# fpga.net
KiCad netlist of a schematic drawn in EAGLE
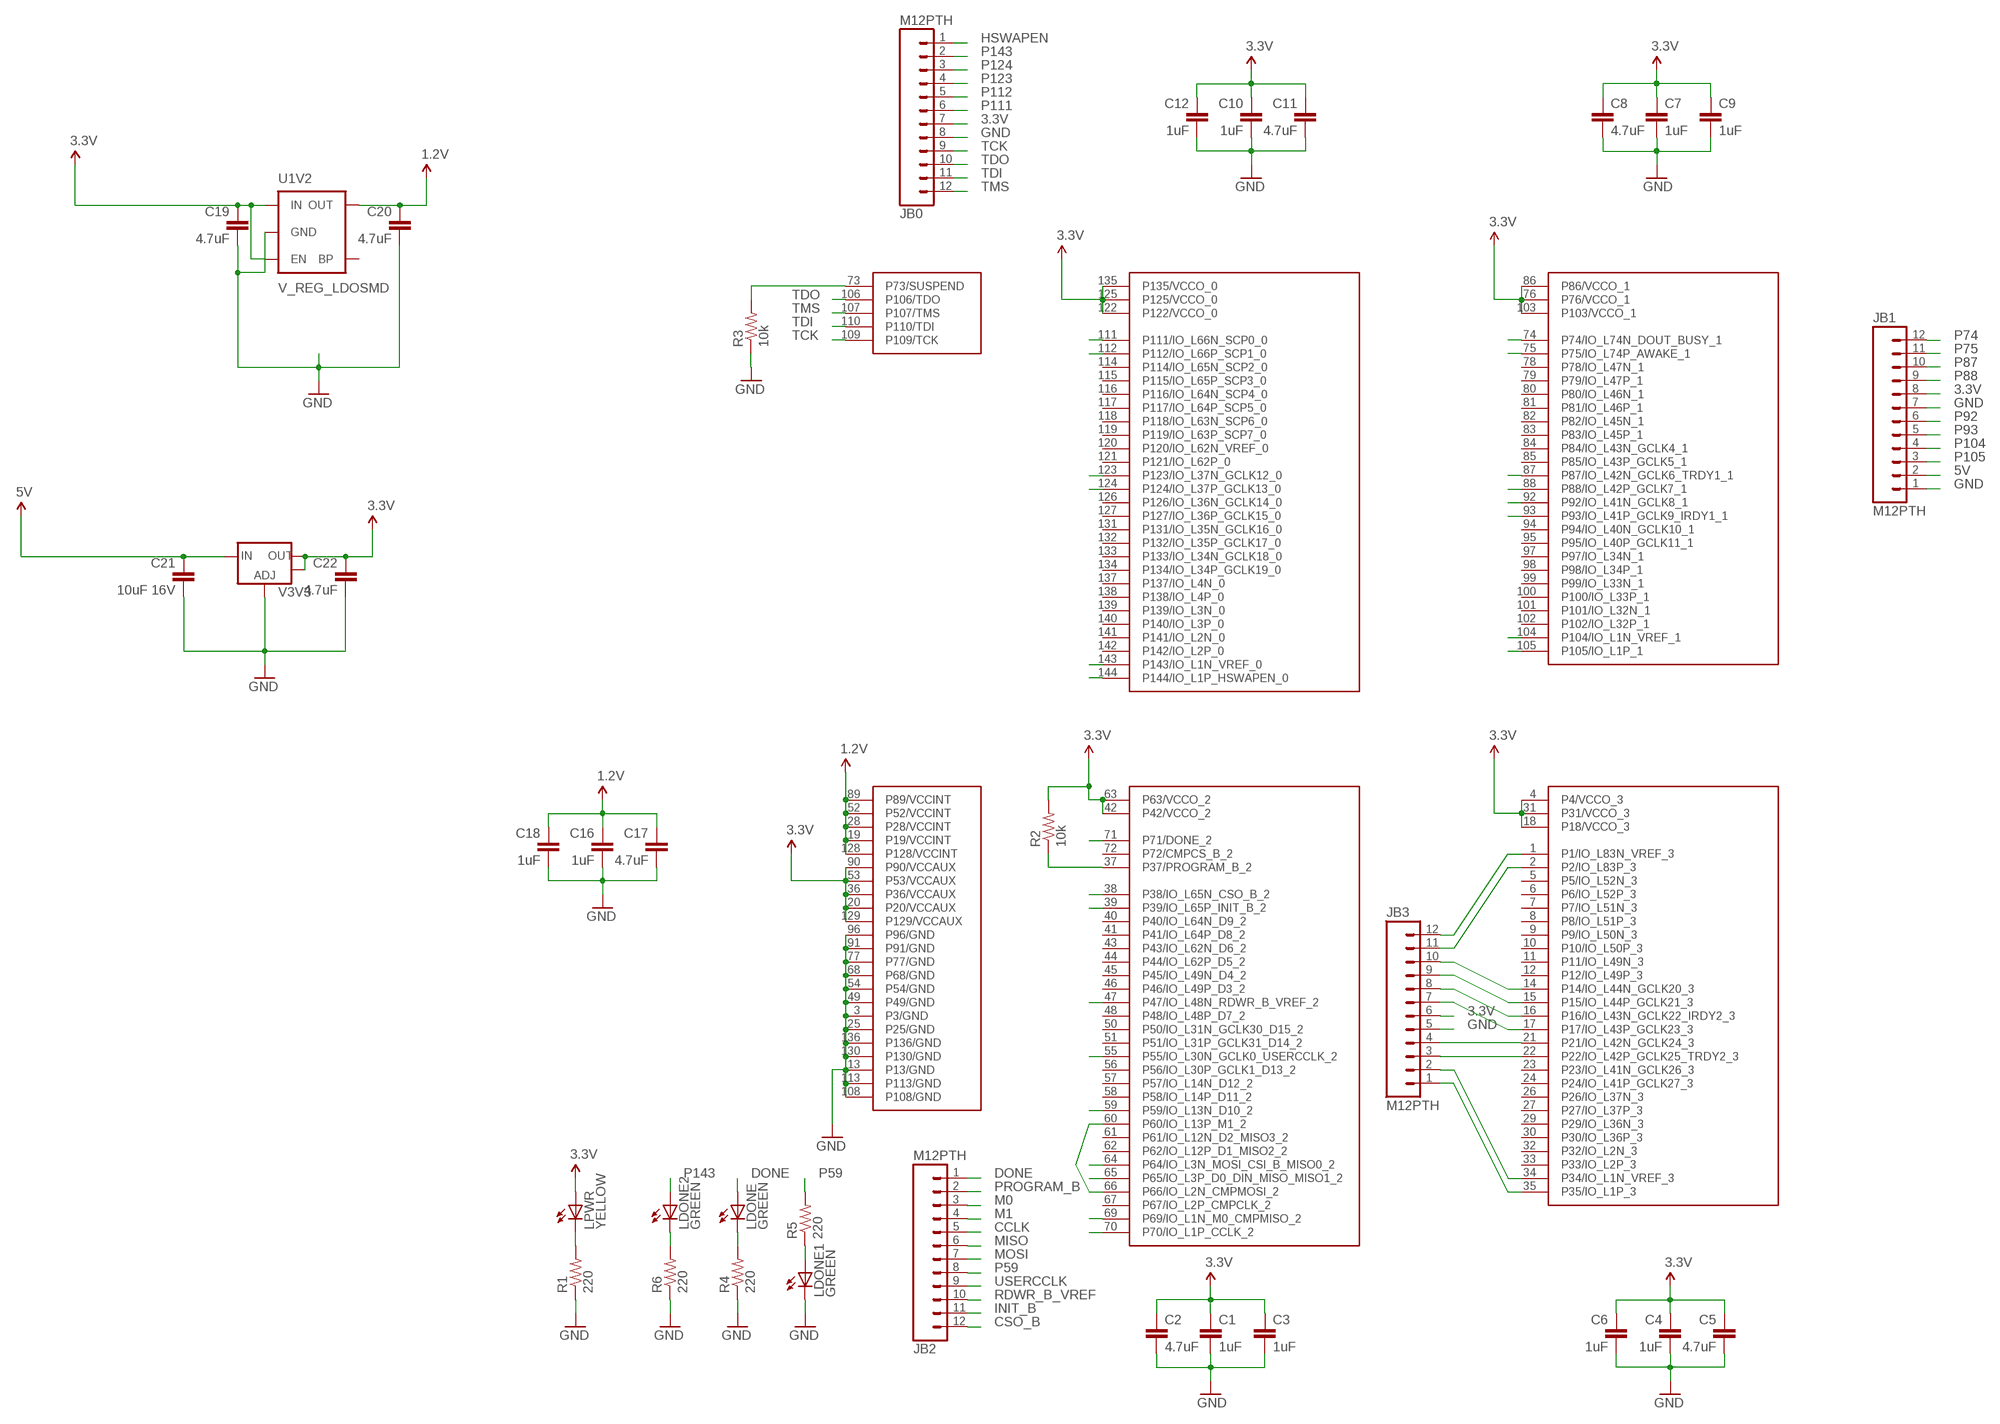
[diagram p0: schematic, sheet 1]

(export (version "E")
  (design (tool "Eeschema 10.0.6"))
  (components
    (comp (ref "C1")
      (value "1uF")
      (footprint "eagle-import:0402-CAP")
      (libsource (lib "eagle-import") (part "CAP0402-CAP"))
    )
    (comp (ref "C2")
      (value "4.7uF")
      (footprint "eagle-import:0805")
      (libsource (lib "eagle-import") (part "kmod_CAP0805"))
    )
    (comp (ref "C3")
      (value "1uF")
      (footprint "eagle-import:0402-CAP")
      (libsource (lib "eagle-import") (part "CAP0402-CAP"))
    )
    (comp (ref "C4")
      (value "1uF")
      (footprint "eagle-import:0402-CAP")
      (libsource (lib "eagle-import") (part "CAP0402-CAP"))
    )
    (comp (ref "C5")
      (value "4.7uF")
      (footprint "eagle-import:0805")
      (libsource (lib "eagle-import") (part "kmod_CAP0805"))
    )
    (comp (ref "C6")
      (value "1uF")
      (footprint "eagle-import:0402-CAP")
      (libsource (lib "eagle-import") (part "CAP0402-CAP"))
    )
    (comp (ref "C7")
      (value "1uF")
      (footprint "eagle-import:0402-CAP")
      (libsource (lib "eagle-import") (part "CAP0402-CAP"))
    )
    (comp (ref "C8")
      (value "4.7uF")
      (footprint "eagle-import:0805")
      (libsource (lib "eagle-import") (part "kmod_CAP0805"))
    )
    (comp (ref "C9")
      (value "1uF")
      (footprint "eagle-import:0402-CAP")
      (libsource (lib "eagle-import") (part "CAP0402-CAP"))
    )
    (comp (ref "C10")
      (value "1uF")
      (footprint "eagle-import:0402-CAP")
      (libsource (lib "eagle-import") (part "CAP0402-CAP"))
    )
    (comp (ref "C11")
      (value "4.7uF")
      (footprint "eagle-import:0805")
      (libsource (lib "eagle-import") (part "kmod_CAP0805"))
    )
    (comp (ref "C12")
      (value "1uF")
      (footprint "eagle-import:0402-CAP")
      (libsource (lib "eagle-import") (part "CAP0402-CAP"))
    )
    (comp (ref "C16")
      (value "1uF")
      (footprint "eagle-import:0402-CAP")
      (libsource (lib "eagle-import") (part "CAP0402-CAP"))
    )
    (comp (ref "C17")
      (value "4.7uF")
      (footprint "eagle-import:0805")
      (libsource (lib "eagle-import") (part "kmod_CAP0805"))
    )
    (comp (ref "C18")
      (value "1uF")
      (footprint "eagle-import:0402-CAP")
      (libsource (lib "eagle-import") (part "CAP0402-CAP"))
    )
    (comp (ref "C19")
      (value "4.7uF")
      (footprint "eagle-import:0805")
      (libsource (lib "eagle-import") (part "kmod_CAP0805"))
    )
    (comp (ref "C20")
      (value "4.7uF")
      (footprint "eagle-import:0805")
      (libsource (lib "eagle-import") (part "kmod_CAP0805"))
    )
    (comp (ref "C21")
      (value "10uF 16V")
      (footprint "eagle-import:0805")
      (libsource (lib "eagle-import") (part "kmod_CAP0805"))
    )
    (comp (ref "C22")
      (value "4.7uF")
      (footprint "eagle-import:0805")
      (libsource (lib "eagle-import") (part "kmod_CAP0805"))
    )
    (comp (ref "JB0")
      (value "M12PTH")
      (footprint "eagle-import:1X12")
      (libsource (lib "eagle-import") (part "M12PTH"))
    )
    (comp (ref "JB1")
      (value "M12PTH")
      (footprint "eagle-import:1X12")
      (libsource (lib "eagle-import") (part "M12PTH"))
    )
    (comp (ref "JB2")
      (value "M12PTH")
      (footprint "eagle-import:1X12")
      (libsource (lib "eagle-import") (part "M12PTH"))
    )
    (comp (ref "JB3")
      (value "M12PTH")
      (footprint "eagle-import:1X12")
      (libsource (lib "eagle-import") (part "M12PTH"))
    )
    (comp (ref "LDONE")
      (value "GREEN")
      (footprint "eagle-import:0603_LED")
      (libsource (lib "eagle-import") (part "LED0603"))
    )
    (comp (ref "LDONE1")
      (value "GREEN")
      (footprint "eagle-import:0603_LED")
      (libsource (lib "eagle-import") (part "LED0603"))
    )
    (comp (ref "LDONE2")
      (value "GREEN")
      (footprint "eagle-import:0603_LED")
      (libsource (lib "eagle-import") (part "LED0603"))
    )
    (comp (ref "LPWR")
      (value "YELLOW")
      (footprint "eagle-import:0603_LED")
      (libsource (lib "eagle-import") (part "LED0603"))
    )
    (comp (ref "R1")
      (value "220")
      (footprint "eagle-import:0603-RES")
      (libsource (lib "eagle-import") (part "RESISTOR0603"))
    )
    (comp (ref "R2")
      (value "10k")
      (footprint "eagle-import:0603-RES")
      (libsource (lib "eagle-import") (part "RESISTOR0603"))
    )
    (comp (ref "R3")
      (value "10k")
      (footprint "eagle-import:0603-RES")
      (libsource (lib "eagle-import") (part "RESISTOR0603"))
    )
    (comp (ref "R4")
      (value "220")
      (footprint "eagle-import:0603-RES")
      (libsource (lib "eagle-import") (part "RESISTOR0603"))
    )
    (comp (ref "R5")
      (value "220")
      (footprint "eagle-import:0603-RES")
      (libsource (lib "eagle-import") (part "RESISTOR0603"))
    )
    (comp (ref "R6")
      (value "220")
      (footprint "eagle-import:0603-RES")
      (libsource (lib "eagle-import") (part "RESISTOR0603"))
    )
    (comp (ref "U$1")
      (value "XC6SLX-TQ144")
      (footprint "eagle-import:XILNX_TQ144")
      (libsource (lib "eagle-import") (part "XC6SLX-TQ144"))
    )
    (comp (ref "U1V2")
      (value "V_REG_LDOSMD")
      (footprint "eagle-import:SOT23-5")
      (libsource (lib "eagle-import") (part "V_REG_LDOSMD"))
    )
    (comp (ref "V3V3")
      (value "V_REG_LM1117SOT223")
      (footprint "eagle-import:SOT223")
      (libsource (lib "eagle-import") (part "V_REG_LM1117SOT223"))
    )
  )
  (nets
    (net (code "1") (name "/CCLK") (class "Default")
      (node (ref "JB2") (pin "5") (pinfunction "5_5") (pintype "passive"))
      (node (ref "U$1") (pin "70") (pinfunction "P70/IO_L1P_CCLK_2_70") (pintype "bidirectional"))
    )
    (net (code "2") (name "/CSO_B") (class "Default")
      (node (ref "JB2") (pin "12") (pinfunction "12_12") (pintype "passive"))
      (node (ref "U$1") (pin "38") (pinfunction "P38/IO_L65N_CSO_B_2_38") (pintype "bidirectional"))
    )
    (net (code "3") (name "/DONE") (class "Default")
      (node (ref "JB2") (pin "1") (pinfunction "1_1") (pintype "passive"))
      (node (ref "LDONE") (pin "A") (pinfunction "A_A") (pintype "passive"))
      (node (ref "U$1") (pin "71") (pinfunction "P71/DONE_2_71") (pintype "bidirectional"))
    )
    (net (code "4") (name "/HSWAPEN") (class "Default")
      (node (ref "JB0") (pin "1") (pinfunction "1_1") (pintype "passive"))
      (node (ref "U$1") (pin "144") (pinfunction "P144/IO_L1P_HSWAPEN_0_144") (pintype "bidirectional"))
    )
    (net (code "5") (name "/INIT_B") (class "Default")
      (node (ref "JB2") (pin "11") (pinfunction "11_11") (pintype "passive"))
      (node (ref "U$1") (pin "39") (pinfunction "P39/IO_L65P_INIT_B_2_39") (pintype "bidirectional"))
    )
    (net (code "6") (name "/M0") (class "Default")
      (node (ref "JB2") (pin "3") (pinfunction "3_3") (pintype "passive"))
      (node (ref "U$1") (pin "69") (pinfunction "P69/IO_L1N_M0_CMPMISO_2_69") (pintype "bidirectional"))
    )
    (net (code "7") (name "/M1") (class "Default")
      (node (ref "JB2") (pin "4") (pinfunction "4_4") (pintype "passive"))
      (node (ref "U$1") (pin "60") (pinfunction "P60/IO_L13P_M1_2_60") (pintype "bidirectional"))
      (node (ref "U$1") (pin "66") (pinfunction "P66/IO_L2N_CMPMOSI_2_66") (pintype "bidirectional"))
    )
    (net (code "8") (name "/MISO") (class "Default")
      (node (ref "JB2") (pin "6") (pinfunction "6_6") (pintype "passive"))
      (node (ref "U$1") (pin "65") (pinfunction "P65/IO_L3P_D0_DIN_MISO_MISO1_2_65") (pintype "bidirectional"))
    )
    (net (code "9") (name "/MOSI") (class "Default")
      (node (ref "JB2") (pin "7") (pinfunction "7_7") (pintype "passive"))
      (node (ref "U$1") (pin "64") (pinfunction "P64/IO_L3N_MOSI_CSI_B_MISO0_2_64") (pintype "bidirectional"))
    )
    (net (code "10") (name "/P59") (class "Default")
      (node (ref "JB2") (pin "8") (pinfunction "8_8") (pintype "passive"))
      (node (ref "R5") (pin "2") (pinfunction "2_2") (pintype "passive"))
      (node (ref "U$1") (pin "59") (pinfunction "P59/IO_L13N_D10_2_59") (pintype "bidirectional"))
    )
    (net (code "11") (name "/P74") (class "Default")
      (node (ref "JB1") (pin "12") (pinfunction "12_12") (pintype "passive"))
      (node (ref "U$1") (pin "74") (pinfunction "P74/IO_L74N_DOUT_BUSY_1_74") (pintype "bidirectional"))
    )
    (net (code "12") (name "/P75") (class "Default")
      (node (ref "JB1") (pin "11") (pinfunction "11_11") (pintype "passive"))
      (node (ref "U$1") (pin "75") (pinfunction "P75/IO_L74P_AWAKE_1_75") (pintype "bidirectional"))
    )
    (net (code "13") (name "/P87") (class "Default")
      (node (ref "JB1") (pin "10") (pinfunction "10_10") (pintype "passive"))
      (node (ref "U$1") (pin "87") (pinfunction "P87/IO_L42N_GCLK6_TRDY1_1_87") (pintype "bidirectional"))
    )
    (net (code "14") (name "/P88") (class "Default")
      (node (ref "JB1") (pin "9") (pinfunction "9_9") (pintype "passive"))
      (node (ref "U$1") (pin "88") (pinfunction "P88/IO_L42P_GCLK7_1_88") (pintype "bidirectional"))
    )
    (net (code "15") (name "/P92") (class "Default")
      (node (ref "JB1") (pin "6") (pinfunction "6_6") (pintype "passive"))
      (node (ref "U$1") (pin "92") (pinfunction "P92/IO_L41N_GCLK8_1_92") (pintype "bidirectional"))
    )
    (net (code "16") (name "/P93") (class "Default")
      (node (ref "JB1") (pin "5") (pinfunction "5_5") (pintype "passive"))
      (node (ref "U$1") (pin "93") (pinfunction "P93/IO_L41P_GCLK9_IRDY1_1_93") (pintype "bidirectional"))
    )
    (net (code "17") (name "/P104") (class "Default")
      (node (ref "JB1") (pin "4") (pinfunction "4_4") (pintype "passive"))
      (node (ref "U$1") (pin "104") (pinfunction "P104/IO_L1N_VREF_1_104") (pintype "bidirectional"))
    )
    (net (code "18") (name "/P105") (class "Default")
      (node (ref "JB1") (pin "3") (pinfunction "3_3") (pintype "passive"))
      (node (ref "U$1") (pin "105") (pinfunction "P105/IO_L1P_1_105") (pintype "bidirectional"))
    )
    (net (code "19") (name "/P111") (class "Default")
      (node (ref "JB0") (pin "6") (pinfunction "6_6") (pintype "passive"))
      (node (ref "U$1") (pin "111") (pinfunction "P111/IO_L66N_SCP0_0_111") (pintype "bidirectional"))
    )
    (net (code "20") (name "/P112") (class "Default")
      (node (ref "JB0") (pin "5") (pinfunction "5_5") (pintype "passive"))
      (node (ref "U$1") (pin "112") (pinfunction "P112/IO_L66P_SCP1_0_112") (pintype "bidirectional"))
    )
    (net (code "21") (name "/P123") (class "Default")
      (node (ref "JB0") (pin "4") (pinfunction "4_4") (pintype "passive"))
      (node (ref "U$1") (pin "123") (pinfunction "P123/IO_L37N_GCLK12_0_123") (pintype "bidirectional"))
    )
    (net (code "22") (name "/P124") (class "Default")
      (node (ref "JB0") (pin "3") (pinfunction "3_3") (pintype "passive"))
      (node (ref "U$1") (pin "124") (pinfunction "P124/IO_L37P_GCLK13_0_124") (pintype "bidirectional"))
    )
    (net (code "23") (name "/P143") (class "Default")
      (node (ref "JB0") (pin "2") (pinfunction "2_2") (pintype "passive"))
      (node (ref "LDONE2") (pin "A") (pinfunction "A_A") (pintype "passive"))
      (node (ref "U$1") (pin "143") (pinfunction "P143/IO_L1N_VREF_0_143") (pintype "bidirectional"))
    )
    (net (code "24") (name "/PROGRAM_B") (class "Default")
      (node (ref "JB2") (pin "2") (pinfunction "2_2") (pintype "passive"))
      (node (ref "R2") (pin "1") (pinfunction "1_1") (pintype "passive"))
      (node (ref "U$1") (pin "37") (pinfunction "P37/PROGRAM_B_2_37") (pintype "bidirectional"))
    )
    (net (code "25") (name "/RDWR_B_VREF") (class "Default")
      (node (ref "JB2") (pin "10") (pinfunction "10_10") (pintype "passive"))
      (node (ref "U$1") (pin "47") (pinfunction "P47/IO_L48N_RDWR_B_VREF_2_47") (pintype "bidirectional"))
    )
    (net (code "26") (name "/TCK") (class "Default")
      (node (ref "JB0") (pin "9") (pinfunction "9_9") (pintype "passive"))
      (node (ref "U$1") (pin "109") (pinfunction "P109/TCK_109") (pintype "bidirectional"))
    )
    (net (code "27") (name "/TDI") (class "Default")
      (node (ref "JB0") (pin "11") (pinfunction "11_11") (pintype "passive"))
      (node (ref "U$1") (pin "110") (pinfunction "P110/TDI_110") (pintype "bidirectional"))
    )
    (net (code "28") (name "/TDO") (class "Default")
      (node (ref "JB0") (pin "10") (pinfunction "10_10") (pintype "passive"))
      (node (ref "U$1") (pin "106") (pinfunction "P106/TDO_106") (pintype "bidirectional"))
    )
    (net (code "29") (name "/TMS") (class "Default")
      (node (ref "JB0") (pin "12") (pinfunction "12_12") (pintype "passive"))
      (node (ref "U$1") (pin "107") (pinfunction "P107/TMS_107") (pintype "bidirectional"))
    )
    (net (code "30") (name "/USERCCLK") (class "Default")
      (node (ref "JB2") (pin "9") (pinfunction "9_9") (pintype "passive"))
      (node (ref "U$1") (pin "55") (pinfunction "P55/IO_L30N_GCLK0_USERCCLK_2_55") (pintype "bidirectional"))
    )
    (net (code "31") (name "1.2V") (class "Default")
      (node (ref "C16") (pin "1") (pinfunction "1_1") (pintype "passive"))
      (node (ref "C17") (pin "1") (pinfunction "1_1") (pintype "passive"))
      (node (ref "C18") (pin "1") (pinfunction "1_1") (pintype "passive"))
      (node (ref "C20") (pin "1") (pinfunction "1_1") (pintype "passive"))
      (node (ref "U$1") (pin "128") (pinfunction "P128/VCCINT_128") (pintype "bidirectional"))
      (node (ref "U$1") (pin "19") (pinfunction "P19/VCCINT_19") (pintype "bidirectional"))
      (node (ref "U$1") (pin "28") (pinfunction "P28/VCCINT_28") (pintype "bidirectional"))
      (node (ref "U$1") (pin "52") (pinfunction "P52/VCCINT_52") (pintype "bidirectional"))
      (node (ref "U$1") (pin "89") (pinfunction "P89/VCCINT_89") (pintype "bidirectional"))
      (node (ref "U1V2") (pin "5") (pinfunction "OUT_5") (pintype "passive"))
    )
    (net (code "32") (name "3.3V") (class "Default")
      (node (ref "C1") (pin "1") (pinfunction "1_1") (pintype "passive"))
      (node (ref "C10") (pin "1") (pinfunction "1_1") (pintype "passive"))
      (node (ref "C11") (pin "1") (pinfunction "1_1") (pintype "passive"))
      (node (ref "C12") (pin "1") (pinfunction "1_1") (pintype "passive"))
      (node (ref "C19") (pin "1") (pinfunction "1_1") (pintype "passive"))
      (node (ref "C2") (pin "1") (pinfunction "1_1") (pintype "passive"))
      (node (ref "C22") (pin "1") (pinfunction "1_1") (pintype "passive"))
      (node (ref "C3") (pin "1") (pinfunction "1_1") (pintype "passive"))
      (node (ref "C4") (pin "1") (pinfunction "1_1") (pintype "passive"))
      (node (ref "C5") (pin "1") (pinfunction "1_1") (pintype "passive"))
      (node (ref "C6") (pin "1") (pinfunction "1_1") (pintype "passive"))
      (node (ref "C7") (pin "1") (pinfunction "1_1") (pintype "passive"))
      (node (ref "C8") (pin "1") (pinfunction "1_1") (pintype "passive"))
      (node (ref "C9") (pin "1") (pinfunction "1_1") (pintype "passive"))
      (node (ref "JB0") (pin "7") (pinfunction "7_7") (pintype "passive"))
      (node (ref "JB1") (pin "8") (pinfunction "8_8") (pintype "passive"))
      (node (ref "JB3") (pin "6") (pinfunction "6_6") (pintype "passive"))
      (node (ref "LPWR") (pin "A") (pinfunction "A_A") (pintype "passive"))
      (node (ref "R2") (pin "2") (pinfunction "2_2") (pintype "passive"))
      (node (ref "U$1") (pin "103") (pinfunction "P103/VCCO_1_103") (pintype "bidirectional"))
      (node (ref "U$1") (pin "122") (pinfunction "P122/VCCO_0_122") (pintype "bidirectional"))
      (node (ref "U$1") (pin "125") (pinfunction "P125/VCCO_0_125") (pintype "bidirectional"))
      (node (ref "U$1") (pin "129") (pinfunction "P129/VCCAUX_129") (pintype "bidirectional"))
      (node (ref "U$1") (pin "135") (pinfunction "P135/VCCO_0_135") (pintype "bidirectional"))
      (node (ref "U$1") (pin "18") (pinfunction "P18/VCCO_3_18") (pintype "bidirectional"))
      (node (ref "U$1") (pin "20") (pinfunction "P20/VCCAUX_20") (pintype "bidirectional"))
      (node (ref "U$1") (pin "31") (pinfunction "P31/VCCO_3_31") (pintype "bidirectional"))
      (node (ref "U$1") (pin "36") (pinfunction "P36/VCCAUX_36") (pintype "bidirectional"))
      (node (ref "U$1") (pin "4") (pinfunction "P4/VCCO_3_4") (pintype "bidirectional"))
      (node (ref "U$1") (pin "42") (pinfunction "P42/VCCO_2_42") (pintype "bidirectional"))
      (node (ref "U$1") (pin "53") (pinfunction "P53/VCCAUX_53") (pintype "bidirectional"))
      (node (ref "U$1") (pin "63") (pinfunction "P63/VCCO_2_63") (pintype "bidirectional"))
      (node (ref "U$1") (pin "76") (pinfunction "P76/VCCO_1_76") (pintype "bidirectional"))
      (node (ref "U$1") (pin "86") (pinfunction "P86/VCCO_1_86") (pintype "bidirectional"))
      (node (ref "U$1") (pin "90") (pinfunction "P90/VCCAUX_90") (pintype "bidirectional"))
      (node (ref "U1V2") (pin "1") (pinfunction "IN_1") (pintype "input"))
      (node (ref "U1V2") (pin "3") (pinfunction "EN_3") (pintype "input"))
      (node (ref "V3V3") (pin "2") (pinfunction "OUT_2") (pintype "output"))
      (node (ref "V3V3") (pin "4") (pinfunction "OUT_4") (pintype "output"))
    )
    (net (code "33") (name "5V") (class "Default")
      (node (ref "C21") (pin "1") (pinfunction "1_1") (pintype "passive"))
      (node (ref "JB1") (pin "2") (pinfunction "2_2") (pintype "passive"))
      (node (ref "V3V3") (pin "3") (pinfunction "IN_3") (pintype "input"))
    )
    (net (code "34") (name "GND") (class "Default")
      (node (ref "C1") (pin "2") (pinfunction "2_2") (pintype "passive"))
      (node (ref "C10") (pin "2") (pinfunction "2_2") (pintype "passive"))
      (node (ref "C11") (pin "2") (pinfunction "2_2") (pintype "passive"))
      (node (ref "C12") (pin "2") (pinfunction "2_2") (pintype "passive"))
      (node (ref "C16") (pin "2") (pinfunction "2_2") (pintype "passive"))
      (node (ref "C17") (pin "2") (pinfunction "2_2") (pintype "passive"))
      (node (ref "C18") (pin "2") (pinfunction "2_2") (pintype "passive"))
      (node (ref "C19") (pin "2") (pinfunction "2_2") (pintype "passive"))
      (node (ref "C2") (pin "2") (pinfunction "2_2") (pintype "passive"))
      (node (ref "C20") (pin "2") (pinfunction "2_2") (pintype "passive"))
      (node (ref "C21") (pin "2") (pinfunction "2_2") (pintype "passive"))
      (node (ref "C22") (pin "2") (pinfunction "2_2") (pintype "passive"))
      (node (ref "C3") (pin "2") (pinfunction "2_2") (pintype "passive"))
      (node (ref "C4") (pin "2") (pinfunction "2_2") (pintype "passive"))
      (node (ref "C5") (pin "2") (pinfunction "2_2") (pintype "passive"))
      (node (ref "C6") (pin "2") (pinfunction "2_2") (pintype "passive"))
      (node (ref "C7") (pin "2") (pinfunction "2_2") (pintype "passive"))
      (node (ref "C8") (pin "2") (pinfunction "2_2") (pintype "passive"))
      (node (ref "C9") (pin "2") (pinfunction "2_2") (pintype "passive"))
      (node (ref "JB0") (pin "8") (pinfunction "8_8") (pintype "passive"))
      (node (ref "JB1") (pin "1") (pinfunction "1_1") (pintype "passive"))
      (node (ref "JB1") (pin "7") (pinfunction "7_7") (pintype "passive"))
      (node (ref "JB3") (pin "5") (pinfunction "5_5") (pintype "passive"))
      (node (ref "LDONE1") (pin "C") (pinfunction "C_C") (pintype "passive"))
      (node (ref "R1") (pin "1") (pinfunction "1_1") (pintype "passive"))
      (node (ref "R3") (pin "1") (pinfunction "1_1") (pintype "passive"))
      (node (ref "R4") (pin "1") (pinfunction "1_1") (pintype "passive"))
      (node (ref "R6") (pin "1") (pinfunction "1_1") (pintype "passive"))
      (node (ref "U$1") (pin "108") (pinfunction "P108/GND_108") (pintype "bidirectional"))
      (node (ref "U$1") (pin "113") (pinfunction "P113/GND_113") (pintype "bidirectional"))
      (node (ref "U$1") (pin "13") (pinfunction "P13/GND_13") (pintype "bidirectional"))
      (node (ref "U$1") (pin "130") (pinfunction "P130/GND_130") (pintype "bidirectional"))
      (node (ref "U$1") (pin "136") (pinfunction "P136/GND_136") (pintype "bidirectional"))
      (node (ref "U$1") (pin "25") (pinfunction "P25/GND_25") (pintype "bidirectional"))
      (node (ref "U$1") (pin "3") (pinfunction "P3/GND_3") (pintype "bidirectional"))
      (node (ref "U$1") (pin "49") (pinfunction "P49/GND_49") (pintype "bidirectional"))
      (node (ref "U$1") (pin "54") (pinfunction "P54/GND_54") (pintype "bidirectional"))
      (node (ref "U$1") (pin "68") (pinfunction "P68/GND_68") (pintype "bidirectional"))
      (node (ref "U$1") (pin "77") (pinfunction "P77/GND_77") (pintype "bidirectional"))
      (node (ref "U$1") (pin "91") (pinfunction "P91/GND_91") (pintype "bidirectional"))
      (node (ref "U$1") (pin "96") (pinfunction "P96/GND_96") (pintype "bidirectional"))
      (node (ref "U1V2") (pin "2") (pinfunction "GND_2") (pintype "input"))
      (node (ref "V3V3") (pin "1") (pinfunction "ADJ_1") (pintype "input"))
    )
    (net (code "35") (name "Net-(LDONE-PadC)") (class "Default")
      (node (ref "LDONE") (pin "C") (pinfunction "C_C") (pintype "passive"))
      (node (ref "R4") (pin "2") (pinfunction "2_2") (pintype "passive"))
    )
    (net (code "36") (name "Net-(LDONE1-PadA)") (class "Default")
      (node (ref "LDONE1") (pin "A") (pinfunction "A_A") (pintype "passive"))
      (node (ref "R5") (pin "1") (pinfunction "1_1") (pintype "passive"))
    )
    (net (code "37") (name "Net-(LDONE2-PadC)") (class "Default")
      (node (ref "LDONE2") (pin "C") (pinfunction "C_C") (pintype "passive"))
      (node (ref "R6") (pin "2") (pinfunction "2_2") (pintype "passive"))
    )
    (net (code "38") (name "Net-(LPWR-PadC)") (class "Default")
      (node (ref "LPWR") (pin "C") (pinfunction "C_C") (pintype "passive"))
      (node (ref "R1") (pin "2") (pinfunction "2_2") (pintype "passive"))
    )
    (net (code "39") (name "Net-(U$1-P1{slash}IO_L83N_VREF_3)") (class "Default")
      (node (ref "JB3") (pin "12") (pinfunction "12_12") (pintype "passive"))
      (node (ref "U$1") (pin "1") (pinfunction "P1/IO_L83N_VREF_3_1") (pintype "bidirectional"))
    )
    (net (code "40") (name "Net-(U$1-P2{slash}IO_L83P_3)") (class "Default")
      (node (ref "JB3") (pin "11") (pinfunction "11_11") (pintype "passive"))
      (node (ref "U$1") (pin "2") (pinfunction "P2/IO_L83P_3_2") (pintype "bidirectional"))
    )
    (net (code "41") (name "Net-(U$1-P14{slash}IO_L44N_GCLK20_3)") (class "Default")
      (node (ref "JB3") (pin "10") (pinfunction "10_10") (pintype "passive"))
      (node (ref "U$1") (pin "14") (pinfunction "P14/IO_L44N_GCLK20_3_14") (pintype "bidirectional"))
    )
    (net (code "42") (name "Net-(U$1-P15{slash}IO_L44P_GCLK21_3)") (class "Default")
      (node (ref "JB3") (pin "9") (pinfunction "9_9") (pintype "passive"))
      (node (ref "U$1") (pin "15") (pinfunction "P15/IO_L44P_GCLK21_3_15") (pintype "bidirectional"))
    )
    (net (code "43") (name "Net-(U$1-P16{slash}IO_L43N_GCLK22_IRDY2_3)") (class "Default")
      (node (ref "JB3") (pin "8") (pinfunction "8_8") (pintype "passive"))
      (node (ref "U$1") (pin "16") (pinfunction "P16/IO_L43N_GCLK22_IRDY2_3_16") (pintype "bidirectional"))
    )
    (net (code "44") (name "Net-(U$1-P17{slash}IO_L43P_GCLK23_3)") (class "Default")
      (node (ref "JB3") (pin "7") (pinfunction "7_7") (pintype "passive"))
      (node (ref "U$1") (pin "17") (pinfunction "P17/IO_L43P_GCLK23_3_17") (pintype "bidirectional"))
    )
    (net (code "45") (name "Net-(U$1-P21{slash}IO_L42N_GCLK24_3)") (class "Default")
      (node (ref "JB3") (pin "4") (pinfunction "4_4") (pintype "passive"))
      (node (ref "U$1") (pin "21") (pinfunction "P21/IO_L42N_GCLK24_3_21") (pintype "bidirectional"))
    )
    (net (code "46") (name "Net-(U$1-P22{slash}IO_L42P_GCLK25_TRDY2_3)") (class "Default")
      (node (ref "JB3") (pin "3") (pinfunction "3_3") (pintype "passive"))
      (node (ref "U$1") (pin "22") (pinfunction "P22/IO_L42P_GCLK25_TRDY2_3_22") (pintype "bidirectional"))
    )
    (net (code "47") (name "Net-(U$1-P34{slash}IO_L1N_VREF_3)") (class "Default")
      (node (ref "JB3") (pin "2") (pinfunction "2_2") (pintype "passive"))
      (node (ref "U$1") (pin "34") (pinfunction "P34/IO_L1N_VREF_3_34") (pintype "bidirectional"))
    )
    (net (code "48") (name "Net-(U$1-P35{slash}IO_L1P_3)") (class "Default")
      (node (ref "JB3") (pin "1") (pinfunction "1_1") (pintype "passive"))
      (node (ref "U$1") (pin "35") (pinfunction "P35/IO_L1P_3_35") (pintype "bidirectional"))
    )
    (net (code "49") (name "Net-(U$1-P73{slash}SUSPEND)") (class "Default")
      (node (ref "R3") (pin "2") (pinfunction "2_2") (pintype "passive"))
      (node (ref "U$1") (pin "73") (pinfunction "P73/SUSPEND_73") (pintype "bidirectional"))
    )
    (net (code "50") (name "unconnected-(U$1-P5{slash}IO_L52N_3-Pad5)") (class "Default")
      (node (ref "U$1") (pin "5") (pinfunction "P5/IO_L52N_3_5") (pintype "bidirectional"))
    )
    (net (code "51") (name "unconnected-(U$1-P6{slash}IO_L52P_3-Pad6)") (class "Default")
      (node (ref "U$1") (pin "6") (pinfunction "P6/IO_L52P_3_6") (pintype "bidirectional"))
    )
    (net (code "52") (name "unconnected-(U$1-P7{slash}IO_L51N_3-Pad7)") (class "Default")
      (node (ref "U$1") (pin "7") (pinfunction "P7/IO_L51N_3_7") (pintype "bidirectional"))
    )
    (net (code "53") (name "unconnected-(U$1-P8{slash}IO_L51P_3-Pad8)") (class "Default")
      (node (ref "U$1") (pin "8") (pinfunction "P8/IO_L51P_3_8") (pintype "bidirectional"))
    )
    (net (code "54") (name "unconnected-(U$1-P9{slash}IO_L50N_3-Pad9)") (class "Default")
      (node (ref "U$1") (pin "9") (pinfunction "P9/IO_L50N_3_9") (pintype "bidirectional"))
    )
    (net (code "55") (name "unconnected-(U$1-P10{slash}IO_L50P_3-Pad10)") (class "Default")
      (node (ref "U$1") (pin "10") (pinfunction "P10/IO_L50P_3_10") (pintype "bidirectional"))
    )
    (net (code "56") (name "unconnected-(U$1-P11{slash}IO_L49N_3-Pad11)") (class "Default")
      (node (ref "U$1") (pin "11") (pinfunction "P11/IO_L49N_3_11") (pintype "bidirectional"))
    )
    (net (code "57") (name "unconnected-(U$1-P12{slash}IO_L49P_3-Pad12)") (class "Default")
      (node (ref "U$1") (pin "12") (pinfunction "P12/IO_L49P_3_12") (pintype "bidirectional"))
    )
    (net (code "58") (name "unconnected-(U$1-P23{slash}IO_L41N_GCLK26_3-Pad23)") (class "Default")
      (node (ref "U$1") (pin "23") (pinfunction "P23/IO_L41N_GCLK26_3_23") (pintype "bidirectional"))
    )
    (net (code "59") (name "unconnected-(U$1-P24{slash}IO_L41P_GCLK27_3-Pad24)") (class "Default")
      (node (ref "U$1") (pin "24") (pinfunction "P24/IO_L41P_GCLK27_3_24") (pintype "bidirectional"))
    )
    (net (code "60") (name "unconnected-(U$1-P26{slash}IO_L37N_3-Pad26)") (class "Default")
      (node (ref "U$1") (pin "26") (pinfunction "P26/IO_L37N_3_26") (pintype "bidirectional"))
    )
    (net (code "61") (name "unconnected-(U$1-P27{slash}IO_L37P_3-Pad27)") (class "Default")
      (node (ref "U$1") (pin "27") (pinfunction "P27/IO_L37P_3_27") (pintype "bidirectional"))
    )
    (net (code "62") (name "unconnected-(U$1-P29{slash}IO_L36N_3-Pad29)") (class "Default")
      (node (ref "U$1") (pin "29") (pinfunction "P29/IO_L36N_3_29") (pintype "bidirectional"))
    )
    (net (code "63") (name "unconnected-(U$1-P30{slash}IO_L36P_3-Pad30)") (class "Default")
      (node (ref "U$1") (pin "30") (pinfunction "P30/IO_L36P_3_30") (pintype "bidirectional"))
    )
    (net (code "64") (name "unconnected-(U$1-P32{slash}IO_L2N_3-Pad32)") (class "Default")
      (node (ref "U$1") (pin "32") (pinfunction "P32/IO_L2N_3_32") (pintype "bidirectional"))
    )
    (net (code "65") (name "unconnected-(U$1-P33{slash}IO_L2P_3-Pad33)") (class "Default")
      (node (ref "U$1") (pin "33") (pinfunction "P33/IO_L2P_3_33") (pintype "bidirectional"))
    )
    (net (code "66") (name "unconnected-(U$1-P40{slash}IO_L64N_D9_2-Pad40)") (class "Default")
      (node (ref "U$1") (pin "40") (pinfunction "P40/IO_L64N_D9_2_40") (pintype "bidirectional"))
    )
    (net (code "67") (name "unconnected-(U$1-P41{slash}IO_L64P_D8_2-Pad41)") (class "Default")
      (node (ref "U$1") (pin "41") (pinfunction "P41/IO_L64P_D8_2_41") (pintype "bidirectional"))
    )
    (net (code "68") (name "unconnected-(U$1-P43{slash}IO_L62N_D6_2-Pad43)") (class "Default")
      (node (ref "U$1") (pin "43") (pinfunction "P43/IO_L62N_D6_2_43") (pintype "bidirectional"))
    )
    (net (code "69") (name "unconnected-(U$1-P44{slash}IO_L62P_D5_2-Pad44)") (class "Default")
      (node (ref "U$1") (pin "44") (pinfunction "P44/IO_L62P_D5_2_44") (pintype "bidirectional"))
    )
    (net (code "70") (name "unconnected-(U$1-P45{slash}IO_L49N_D4_2-Pad45)") (class "Default")
      (node (ref "U$1") (pin "45") (pinfunction "P45/IO_L49N_D4_2_45") (pintype "bidirectional"))
    )
    (net (code "71") (name "unconnected-(U$1-P46{slash}IO_L49P_D3_2-Pad46)") (class "Default")
      (node (ref "U$1") (pin "46") (pinfunction "P46/IO_L49P_D3_2_46") (pintype "bidirectional"))
    )
    (net (code "72") (name "unconnected-(U$1-P48{slash}IO_L48P_D7_2-Pad48)") (class "Default")
      (node (ref "U$1") (pin "48") (pinfunction "P48/IO_L48P_D7_2_48") (pintype "bidirectional"))
    )
    (net (code "73") (name "unconnected-(U$1-P50{slash}IO_L31N_GCLK30_D15_2-Pad50)") (class "Default")
      (node (ref "U$1") (pin "50") (pinfunction "P50/IO_L31N_GCLK30_D15_2_50") (pintype "bidirectional"))
    )
    (net (code "74") (name "unconnected-(U$1-P51{slash}IO_L31P_GCLK31_D14_2-Pad51)") (class "Default")
      (node (ref "U$1") (pin "51") (pinfunction "P51/IO_L31P_GCLK31_D14_2_51") (pintype "bidirectional"))
    )
    (net (code "75") (name "unconnected-(U$1-P56{slash}IO_L30P_GCLK1_D13_2-Pad56)") (class "Default")
      (node (ref "U$1") (pin "56") (pinfunction "P56/IO_L30P_GCLK1_D13_2_56") (pintype "bidirectional"))
    )
    (net (code "76") (name "unconnected-(U$1-P57{slash}IO_L14N_D12_2-Pad57)") (class "Default")
      (node (ref "U$1") (pin "57") (pinfunction "P57/IO_L14N_D12_2_57") (pintype "bidirectional"))
    )
    (net (code "77") (name "unconnected-(U$1-P58{slash}IO_L14P_D11_2-Pad58)") (class "Default")
      (node (ref "U$1") (pin "58") (pinfunction "P58/IO_L14P_D11_2_58") (pintype "bidirectional"))
    )
    (net (code "78") (name "unconnected-(U$1-P61{slash}IO_L12N_D2_MISO3_2-Pad61)") (class "Default")
      (node (ref "U$1") (pin "61") (pinfunction "P61/IO_L12N_D2_MISO3_2_61") (pintype "bidirectional"))
    )
    (net (code "79") (name "unconnected-(U$1-P62{slash}IO_L12P_D1_MISO2_2-Pad62)") (class "Default")
      (node (ref "U$1") (pin "62") (pinfunction "P62/IO_L12P_D1_MISO2_2_62") (pintype "bidirectional"))
    )
    (net (code "80") (name "unconnected-(U$1-P67{slash}IO_L2P_CMPCLK_2-Pad67)") (class "Default")
      (node (ref "U$1") (pin "67") (pinfunction "P67/IO_L2P_CMPCLK_2_67") (pintype "bidirectional"))
    )
    (net (code "81") (name "unconnected-(U$1-P72{slash}CMPCS_B_2-Pad72)") (class "Default")
      (node (ref "U$1") (pin "72") (pinfunction "P72/CMPCS_B_2_72") (pintype "bidirectional"))
    )
    (net (code "82") (name "unconnected-(U$1-P78{slash}IO_L47N_1-Pad78)") (class "Default")
      (node (ref "U$1") (pin "78") (pinfunction "P78/IO_L47N_1_78") (pintype "bidirectional"))
    )
    (net (code "83") (name "unconnected-(U$1-P79{slash}IO_L47P_1-Pad79)") (class "Default")
      (node (ref "U$1") (pin "79") (pinfunction "P79/IO_L47P_1_79") (pintype "bidirectional"))
    )
    (net (code "84") (name "unconnected-(U$1-P80{slash}IO_L46N_1-Pad80)") (class "Default")
      (node (ref "U$1") (pin "80") (pinfunction "P80/IO_L46N_1_80") (pintype "bidirectional"))
    )
    (net (code "85") (name "unconnected-(U$1-P81{slash}IO_L46P_1-Pad81)") (class "Default")
      (node (ref "U$1") (pin "81") (pinfunction "P81/IO_L46P_1_81") (pintype "bidirectional"))
    )
    (net (code "86") (name "unconnected-(U$1-P82{slash}IO_L45N_1-Pad82)") (class "Default")
      (node (ref "U$1") (pin "82") (pinfunction "P82/IO_L45N_1_82") (pintype "bidirectional"))
    )
    (net (code "87") (name "unconnected-(U$1-P83{slash}IO_L45P_1-Pad83)") (class "Default")
      (node (ref "U$1") (pin "83") (pinfunction "P83/IO_L45P_1_83") (pintype "bidirectional"))
    )
    (net (code "88") (name "unconnected-(U$1-P84{slash}IO_L43N_GCLK4_1-Pad84)") (class "Default")
      (node (ref "U$1") (pin "84") (pinfunction "P84/IO_L43N_GCLK4_1_84") (pintype "bidirectional"))
    )
    (net (code "89") (name "unconnected-(U$1-P85{slash}IO_L43P_GCLK5_1-Pad85)") (class "Default")
      (node (ref "U$1") (pin "85") (pinfunction "P85/IO_L43P_GCLK5_1_85") (pintype "bidirectional"))
    )
    (net (code "90") (name "unconnected-(U$1-P94{slash}IO_L40N_GCLK10_1-Pad94)") (class "Default")
      (node (ref "U$1") (pin "94") (pinfunction "P94/IO_L40N_GCLK10_1_94") (pintype "bidirectional"))
    )
    (net (code "91") (name "unconnected-(U$1-P95{slash}IO_L40P_GCLK11_1-Pad95)") (class "Default")
      (node (ref "U$1") (pin "95") (pinfunction "P95/IO_L40P_GCLK11_1_95") (pintype "bidirectional"))
    )
    (net (code "92") (name "unconnected-(U$1-P97{slash}IO_L34N_1-Pad97)") (class "Default")
      (node (ref "U$1") (pin "97") (pinfunction "P97/IO_L34N_1_97") (pintype "bidirectional"))
    )
    (net (code "93") (name "unconnected-(U$1-P98{slash}IO_L34P_1-Pad98)") (class "Default")
      (node (ref "U$1") (pin "98") (pinfunction "P98/IO_L34P_1_98") (pintype "bidirectional"))
    )
    (net (code "94") (name "unconnected-(U$1-P99{slash}IO_L33N_1-Pad99)") (class "Default")
      (node (ref "U$1") (pin "99") (pinfunction "P99/IO_L33N_1_99") (pintype "bidirectional"))
    )
    (net (code "95") (name "unconnected-(U$1-P100{slash}IO_L33P_1-Pad100)") (class "Default")
      (node (ref "U$1") (pin "100") (pinfunction "P100/IO_L33P_1_100") (pintype "bidirectional"))
    )
    (net (code "96") (name "unconnected-(U$1-P101{slash}IO_L32N_1-Pad101)") (class "Default")
      (node (ref "U$1") (pin "101") (pinfunction "P101/IO_L32N_1_101") (pintype "bidirectional"))
    )
    (net (code "97") (name "unconnected-(U$1-P102{slash}IO_L32P_1-Pad102)") (class "Default")
      (node (ref "U$1") (pin "102") (pinfunction "P102/IO_L32P_1_102") (pintype "bidirectional"))
    )
    (net (code "98") (name "unconnected-(U$1-P114{slash}IO_L65N_SCP2_0-Pad114)") (class "Default")
      (node (ref "U$1") (pin "114") (pinfunction "P114/IO_L65N_SCP2_0_114") (pintype "bidirectional"))
    )
    (net (code "99") (name "unconnected-(U$1-P115{slash}IO_L65P_SCP3_0-Pad115)") (class "Default")
      (node (ref "U$1") (pin "115") (pinfunction "P115/IO_L65P_SCP3_0_115") (pintype "bidirectional"))
    )
    (net (code "100") (name "unconnected-(U$1-P116{slash}IO_L64N_SCP4_0-Pad116)") (class "Default")
      (node (ref "U$1") (pin "116") (pinfunction "P116/IO_L64N_SCP4_0_116") (pintype "bidirectional"))
    )
    (net (code "101") (name "unconnected-(U$1-P117{slash}IO_L64P_SCP5_0-Pad117)") (class "Default")
      (node (ref "U$1") (pin "117") (pinfunction "P117/IO_L64P_SCP5_0_117") (pintype "bidirectional"))
    )
    (net (code "102") (name "unconnected-(U$1-P118{slash}IO_L63N_SCP6_0-Pad118)") (class "Default")
      (node (ref "U$1") (pin "118") (pinfunction "P118/IO_L63N_SCP6_0_118") (pintype "bidirectional"))
    )
    (net (code "103") (name "unconnected-(U$1-P119{slash}IO_L63P_SCP7_0-Pad119)") (class "Default")
      (node (ref "U$1") (pin "119") (pinfunction "P119/IO_L63P_SCP7_0_119") (pintype "bidirectional"))
    )
    (net (code "104") (name "unconnected-(U$1-P120{slash}IO_L62N_VREF_0-Pad120)") (class "Default")
      (node (ref "U$1") (pin "120") (pinfunction "P120/IO_L62N_VREF_0_120") (pintype "bidirectional"))
    )
    (net (code "105") (name "unconnected-(U$1-P121{slash}IO_L62P_0-Pad121)") (class "Default")
      (node (ref "U$1") (pin "121") (pinfunction "P121/IO_L62P_0_121") (pintype "bidirectional"))
    )
    (net (code "106") (name "unconnected-(U$1-P126{slash}IO_L36N_GCLK14_0-Pad126)") (class "Default")
      (node (ref "U$1") (pin "126") (pinfunction "P126/IO_L36N_GCLK14_0_126") (pintype "bidirectional"))
    )
    (net (code "107") (name "unconnected-(U$1-P127{slash}IO_L36P_GCLK15_0-Pad127)") (class "Default")
      (node (ref "U$1") (pin "127") (pinfunction "P127/IO_L36P_GCLK15_0_127") (pintype "bidirectional"))
    )
    (net (code "108") (name "unconnected-(U$1-P131{slash}IO_L35N_GCLK16_0-Pad131)") (class "Default")
      (node (ref "U$1") (pin "131") (pinfunction "P131/IO_L35N_GCLK16_0_131") (pintype "bidirectional"))
    )
    (net (code "109") (name "unconnected-(U$1-P132{slash}IO_L35P_GCLK17_0-Pad132)") (class "Default")
      (node (ref "U$1") (pin "132") (pinfunction "P132/IO_L35P_GCLK17_0_132") (pintype "bidirectional"))
    )
    (net (code "110") (name "unconnected-(U$1-P133{slash}IO_L34N_GCLK18_0-Pad133)") (class "Default")
      (node (ref "U$1") (pin "133") (pinfunction "P133/IO_L34N_GCLK18_0_133") (pintype "bidirectional"))
    )
    (net (code "111") (name "unconnected-(U$1-P134{slash}IO_L34P_GCLK19_0-Pad134)") (class "Default")
      (node (ref "U$1") (pin "134") (pinfunction "P134/IO_L34P_GCLK19_0_134") (pintype "bidirectional"))
    )
    (net (code "112") (name "unconnected-(U$1-P137{slash}IO_L4N_0-Pad137)") (class "Default")
      (node (ref "U$1") (pin "137") (pinfunction "P137/IO_L4N_0_137") (pintype "bidirectional"))
    )
    (net (code "113") (name "unconnected-(U$1-P138{slash}IO_L4P_0-Pad138)") (class "Default")
      (node (ref "U$1") (pin "138") (pinfunction "P138/IO_L4P_0_138") (pintype "bidirectional"))
    )
    (net (code "114") (name "unconnected-(U$1-P139{slash}IO_L3N_0-Pad139)") (class "Default")
      (node (ref "U$1") (pin "139") (pinfunction "P139/IO_L3N_0_139") (pintype "bidirectional"))
    )
    (net (code "115") (name "unconnected-(U$1-P140{slash}IO_L3P_0-Pad140)") (class "Default")
      (node (ref "U$1") (pin "140") (pinfunction "P140/IO_L3P_0_140") (pintype "bidirectional"))
    )
    (net (code "116") (name "unconnected-(U$1-P141{slash}IO_L2N_0-Pad141)") (class "Default")
      (node (ref "U$1") (pin "141") (pinfunction "P141/IO_L2N_0_141") (pintype "bidirectional"))
    )
    (net (code "117") (name "unconnected-(U$1-P142{slash}IO_L2P_0-Pad142)") (class "Default")
      (node (ref "U$1") (pin "142") (pinfunction "P142/IO_L2P_0_142") (pintype "bidirectional"))
    )
    (net (code "118") (name "unconnected-(U1V2-BP-Pad4)") (class "Default")
      (node (ref "U1V2") (pin "4") (pinfunction "BP_4") (pintype "input"))
    )
  )
)
